# 362_MiniProj_FullBoard.net
KiCad netlist of a schematic drawn in EAGLE
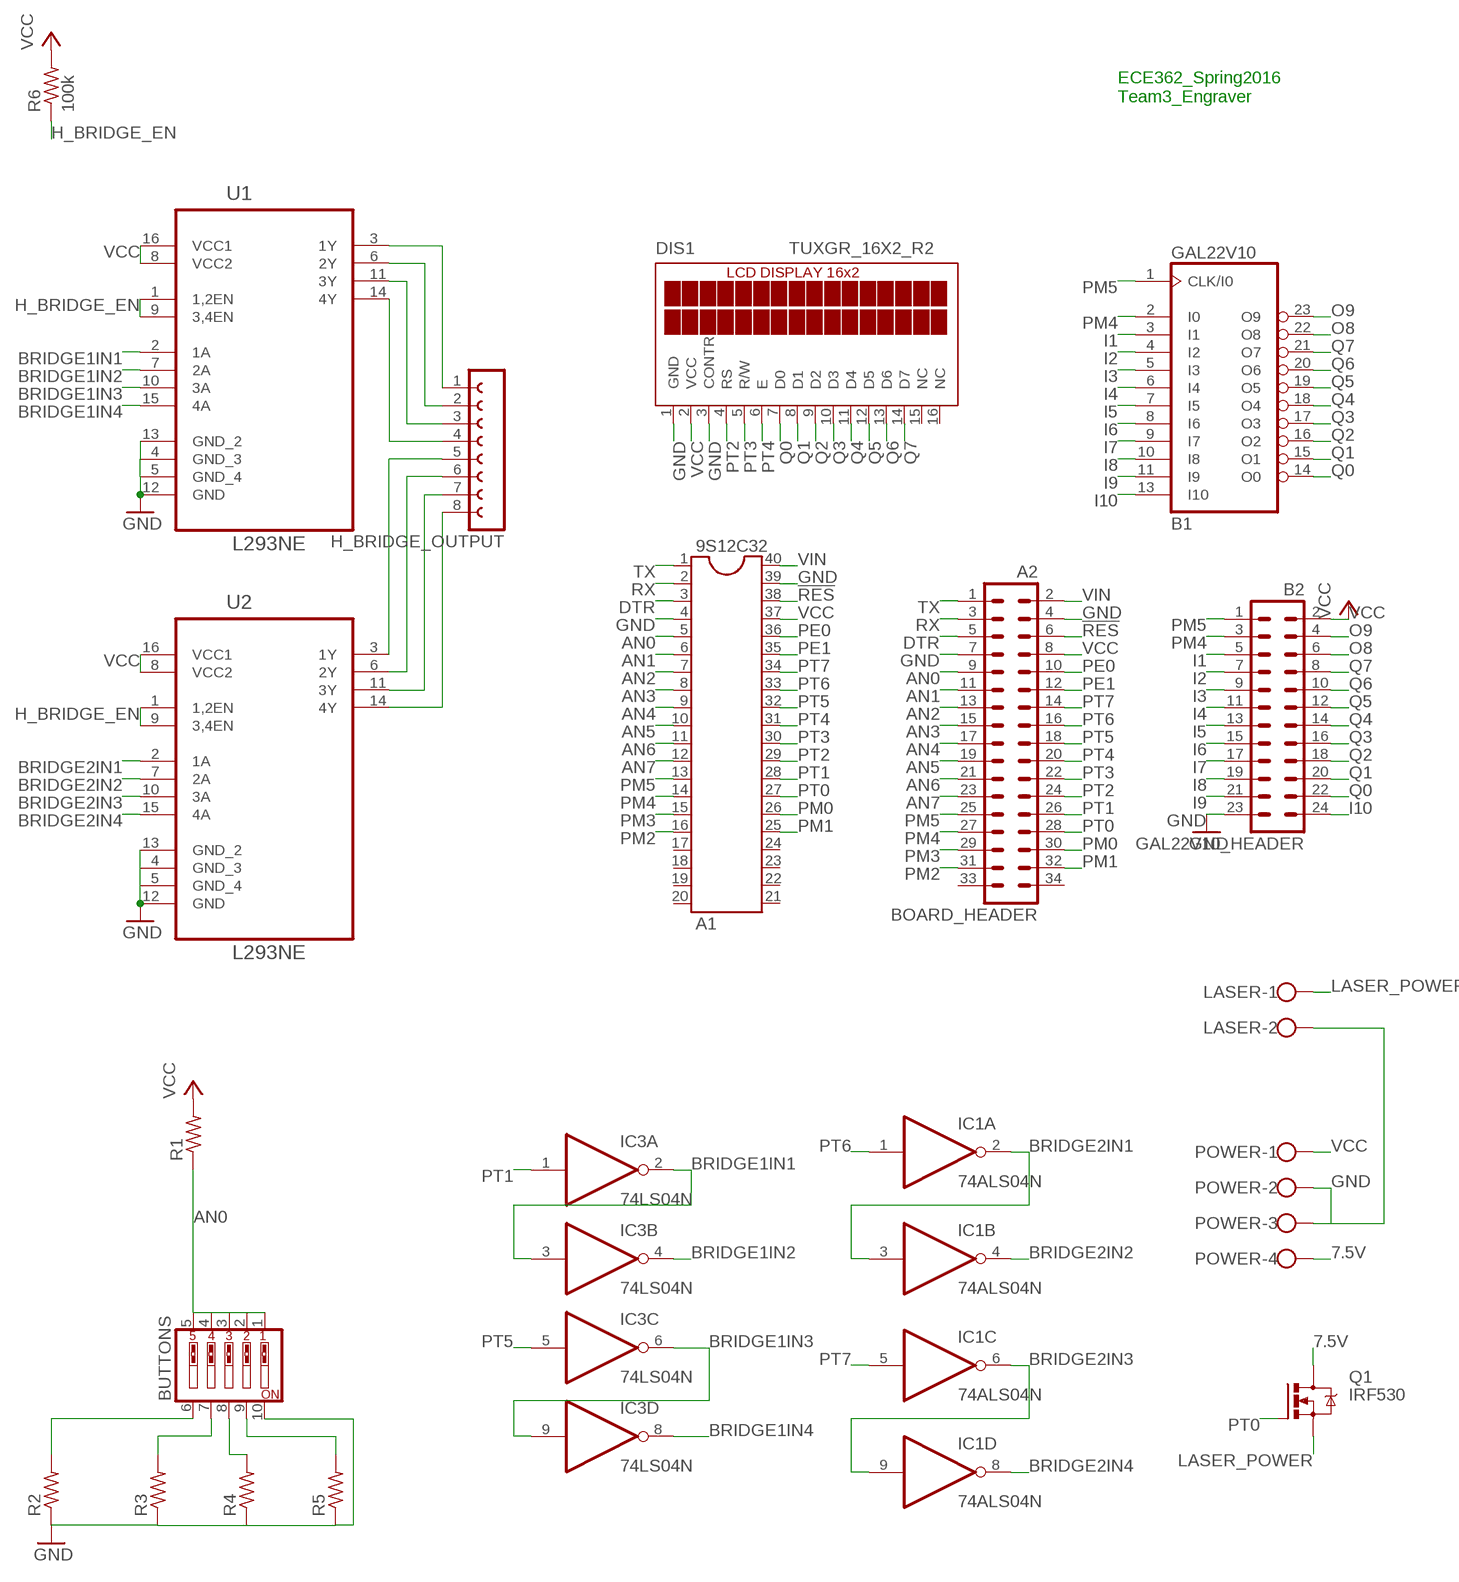
[diagram p0: schematic, sheet 1]

(export (version "E")
  (design (tool "Eeschema 10.0.6"))
  (components
    (comp (ref "9S12C32")
      (value "A1")
      (footprint "eagle-import:DIL40")
      (libsource (lib "eagle-import") (part "DIL40"))
    )
    (comp (ref "BOARD_HEADER")
      (value "A2")
      (footprint "eagle-import:MA17-2")
      (libsource (lib "eagle-import") (part "MA17-2"))
    )
    (comp (ref "BUTTONS")
      (value "SW_DIP-5")
      (footprint "eagle-import:EDG-05")
      (libsource (lib "eagle-import") (part "SW_DIP-5"))
    )
    (comp (ref "DIS1")
      (value "TUXGR_16X2_R2")
      (footprint "eagle-import:TUXGR_16X2_R2")
      (libsource (lib "eagle-import") (part "TUXGR_16X2_R2"))
    )
    (comp (ref "GAL22V10")
      (value "B1")
      (footprint "eagle-import:DIL24-3")
      (fields (field (name "MPN") "GAL22V10D-7LPN"))
      (libsource (lib "eagle-import") (part "22V10"))
    )
    (comp (ref "GAL22V10_HEADER")
      (value "B2")
      (footprint "eagle-import:MA12-2")
      (libsource (lib "eagle-import") (part "MA12-2"))
    )
    (comp (ref "H_BRIDGE_OUTPUT")
      (value "FE08-1")
      (footprint "eagle-import:FE08")
      (libsource (lib "eagle-import") (part "FE08-1"))
    )
    (comp (ref "IC1")
      (value "74ALS04N")
      (footprint "eagle-import:DIL14")
      (libsource (lib "eagle-import") (part "7404NALS"))
    )
    (comp (ref "IC3")
      (value "74LS04N")
      (footprint "eagle-import:DIL14")
      (libsource (lib "eagle-import") (part "74xx-us_7404NLS"))
    )
    (comp (ref "LASER")
      (value "W237-102")
      (footprint "eagle-import:W237-102")
      (fields (field (name "MPN") "237-102"))
      (libsource (lib "eagle-import") (part "W237-102"))
    )
    (comp (ref "POWER")
      (value "W239-104")
      (footprint "eagle-import:W239-104")
      (libsource (lib "eagle-import") (part "W239-104"))
    )
    (comp (ref "Q1")
      (value "IRF530")
      (footprint "eagle-import:TO220BV")
      (libsource (lib "eagle-import") (part "IRF530"))
    )
    (comp (ref "R1")
      (value "R-US_0207/10")
      (footprint "eagle-import:0207_10")
      (libsource (lib "eagle-import") (part "R-US_0207/10"))
    )
    (comp (ref "R2")
      (value "R-US_0207/10")
      (footprint "eagle-import:0207_10")
      (libsource (lib "eagle-import") (part "R-US_0207/10"))
    )
    (comp (ref "R3")
      (value "R-US_0207/10")
      (footprint "eagle-import:0207_10")
      (libsource (lib "eagle-import") (part "R-US_0207/10"))
    )
    (comp (ref "R4")
      (value "R-US_0207/10")
      (footprint "eagle-import:0207_10")
      (libsource (lib "eagle-import") (part "R-US_0207/10"))
    )
    (comp (ref "R5")
      (value "R-US_0207/10")
      (footprint "eagle-import:0207_10")
      (libsource (lib "eagle-import") (part "R-US_0207/10"))
    )
    (comp (ref "R6")
      (value "100k")
      (footprint "eagle-import:0207_10")
      (libsource (lib "eagle-import") (part "R-US_0207/10"))
    )
    (comp (ref "U1")
      (value "L293NE")
      (footprint "eagle-import:DIP254P762X508-16")
      (libsource (lib "eagle-import") (part "L293NE"))
    )
    (comp (ref "U2")
      (value "L293NE")
      (footprint "eagle-import:DIP254P762X508-16")
      (libsource (lib "eagle-import") (part "L293NE"))
    )
  )
  (nets
    (net (code "1") (name "/7.5V") (class "Default")
      (node (ref "POWER") (pin "4") (pinfunction "KL_4") (pintype "passive"))
      (node (ref "Q1") (pin "D") (pinfunction "D_D") (pintype "passive"))
    )
    (net (code "2") (name "/AN0") (class "Default")
      (node (ref "9S12C32") (pin "5") (pinfunction "5_5") (pintype "passive"))
      (node (ref "BOARD_HEADER") (pin "9") (pinfunction "9_9") (pintype "passive"))
      (node (ref "BUTTONS") (pin "1") (pinfunction "1_1") (pintype "passive"))
      (node (ref "BUTTONS") (pin "2") (pinfunction "2_2") (pintype "passive"))
      (node (ref "BUTTONS") (pin "3") (pinfunction "3_3") (pintype "passive"))
      (node (ref "BUTTONS") (pin "4") (pinfunction "4_4") (pintype "passive"))
      (node (ref "BUTTONS") (pin "5") (pinfunction "5_5") (pintype "passive"))
      (node (ref "R1") (pin "1") (pinfunction "1_1") (pintype "passive"))
    )
    (net (code "3") (name "/AN1") (class "Default")
      (node (ref "9S12C32") (pin "6") (pinfunction "6_6") (pintype "passive"))
      (node (ref "BOARD_HEADER") (pin "11") (pinfunction "11_11") (pintype "passive"))
    )
    (net (code "4") (name "/AN2") (class "Default")
      (node (ref "9S12C32") (pin "7") (pinfunction "7_7") (pintype "passive"))
      (node (ref "BOARD_HEADER") (pin "13") (pinfunction "13_13") (pintype "passive"))
    )
    (net (code "5") (name "/AN3") (class "Default")
      (node (ref "9S12C32") (pin "8") (pinfunction "8_8") (pintype "passive"))
      (node (ref "BOARD_HEADER") (pin "15") (pinfunction "15_15") (pintype "passive"))
    )
    (net (code "6") (name "/AN4") (class "Default")
      (node (ref "9S12C32") (pin "9") (pinfunction "9_9") (pintype "passive"))
      (node (ref "BOARD_HEADER") (pin "17") (pinfunction "17_17") (pintype "passive"))
    )
    (net (code "7") (name "/AN5") (class "Default")
      (node (ref "9S12C32") (pin "10") (pinfunction "10_10") (pintype "passive"))
      (node (ref "BOARD_HEADER") (pin "19") (pinfunction "19_19") (pintype "passive"))
    )
    (net (code "8") (name "/AN6") (class "Default")
      (node (ref "9S12C32") (pin "11") (pinfunction "11_11") (pintype "passive"))
      (node (ref "BOARD_HEADER") (pin "21") (pinfunction "21_21") (pintype "passive"))
    )
    (net (code "9") (name "/AN7") (class "Default")
      (node (ref "9S12C32") (pin "12") (pinfunction "12_12") (pintype "passive"))
      (node (ref "BOARD_HEADER") (pin "23") (pinfunction "23_23") (pintype "passive"))
    )
    (net (code "10") (name "/BRIDGE1IN1") (class "Default")
      (node (ref "IC3") (pin "2") (pinfunction "O_2") (pintype "output"))
      (node (ref "IC3") (pin "3") (pinfunction "I_3") (pintype "input"))
      (node (ref "U1") (pin "2") (pinfunction "1A_2") (pintype "input"))
    )
    (net (code "11") (name "/BRIDGE1IN2") (class "Default")
      (node (ref "IC3") (pin "4") (pinfunction "O_4") (pintype "output"))
      (node (ref "U1") (pin "7") (pinfunction "2A_7") (pintype "input"))
    )
    (net (code "12") (name "/BRIDGE1IN3") (class "Default")
      (node (ref "IC3") (pin "6") (pinfunction "O_6") (pintype "output"))
      (node (ref "IC3") (pin "9") (pinfunction "I_9") (pintype "input"))
      (node (ref "U1") (pin "10") (pinfunction "3A_10") (pintype "input"))
    )
    (net (code "13") (name "/BRIDGE1IN4") (class "Default")
      (node (ref "IC3") (pin "8") (pinfunction "O_8") (pintype "output"))
      (node (ref "U1") (pin "15") (pinfunction "4A_15") (pintype "input"))
    )
    (net (code "14") (name "/BRIDGE2IN1") (class "Default")
      (node (ref "IC1") (pin "2") (pinfunction "O_2") (pintype "output"))
      (node (ref "IC1") (pin "3") (pinfunction "I_3") (pintype "input"))
      (node (ref "U2") (pin "2") (pinfunction "1A_2") (pintype "input"))
    )
    (net (code "15") (name "/BRIDGE2IN2") (class "Default")
      (node (ref "IC1") (pin "4") (pinfunction "O_4") (pintype "output"))
      (node (ref "U2") (pin "7") (pinfunction "2A_7") (pintype "input"))
    )
    (net (code "16") (name "/BRIDGE2IN3") (class "Default")
      (node (ref "IC1") (pin "6") (pinfunction "O_6") (pintype "output"))
      (node (ref "IC1") (pin "9") (pinfunction "I_9") (pintype "input"))
      (node (ref "U2") (pin "10") (pinfunction "3A_10") (pintype "input"))
    )
    (net (code "17") (name "/BRIDGE2IN4") (class "Default")
      (node (ref "IC1") (pin "8") (pinfunction "O_8") (pintype "output"))
      (node (ref "U2") (pin "15") (pinfunction "4A_15") (pintype "input"))
    )
    (net (code "18") (name "/DTR") (class "Default")
      (node (ref "9S12C32") (pin "3") (pinfunction "3_3") (pintype "passive"))
      (node (ref "BOARD_HEADER") (pin "5") (pinfunction "5_5") (pintype "passive"))
    )
    (net (code "19") (name "/H_BRIDGE_EN") (class "Default")
      (node (ref "R6") (pin "1") (pinfunction "1_1") (pintype "passive"))
      (node (ref "U1") (pin "1") (pinfunction "1,2EN_1") (pintype "input"))
      (node (ref "U1") (pin "9") (pinfunction "3,4EN_9") (pintype "input"))
      (node (ref "U2") (pin "1") (pinfunction "1,2EN_1") (pintype "input"))
      (node (ref "U2") (pin "9") (pinfunction "3,4EN_9") (pintype "input"))
    )
    (net (code "20") (name "/I1") (class "Default")
      (node (ref "GAL22V10") (pin "3") (pinfunction "I1_3") (pintype "input"))
      (node (ref "GAL22V10_HEADER") (pin "5") (pinfunction "5_5") (pintype "passive"))
    )
    (net (code "21") (name "/I2") (class "Default")
      (node (ref "GAL22V10") (pin "4") (pinfunction "I2_4") (pintype "input"))
      (node (ref "GAL22V10_HEADER") (pin "7") (pinfunction "7_7") (pintype "passive"))
    )
    (net (code "22") (name "/I3") (class "Default")
      (node (ref "GAL22V10") (pin "5") (pinfunction "I3_5") (pintype "input"))
      (node (ref "GAL22V10_HEADER") (pin "9") (pinfunction "9_9") (pintype "passive"))
    )
    (net (code "23") (name "/I4") (class "Default")
      (node (ref "GAL22V10") (pin "6") (pinfunction "I4_6") (pintype "input"))
      (node (ref "GAL22V10_HEADER") (pin "11") (pinfunction "11_11") (pintype "passive"))
    )
    (net (code "24") (name "/I5") (class "Default")
      (node (ref "GAL22V10") (pin "7") (pinfunction "I5_7") (pintype "input"))
      (node (ref "GAL22V10_HEADER") (pin "13") (pinfunction "13_13") (pintype "passive"))
    )
    (net (code "25") (name "/I6") (class "Default")
      (node (ref "GAL22V10") (pin "8") (pinfunction "I6_8") (pintype "input"))
      (node (ref "GAL22V10_HEADER") (pin "15") (pinfunction "15_15") (pintype "passive"))
    )
    (net (code "26") (name "/I7") (class "Default")
      (node (ref "GAL22V10") (pin "9") (pinfunction "I7_9") (pintype "input"))
      (node (ref "GAL22V10_HEADER") (pin "17") (pinfunction "17_17") (pintype "passive"))
    )
    (net (code "27") (name "/I8") (class "Default")
      (node (ref "GAL22V10") (pin "10") (pinfunction "I8_10") (pintype "input"))
      (node (ref "GAL22V10_HEADER") (pin "19") (pinfunction "19_19") (pintype "passive"))
    )
    (net (code "28") (name "/I9") (class "Default")
      (node (ref "GAL22V10") (pin "11") (pinfunction "I9_11") (pintype "input"))
      (node (ref "GAL22V10_HEADER") (pin "21") (pinfunction "21_21") (pintype "passive"))
    )
    (net (code "29") (name "/I10") (class "Default")
      (node (ref "GAL22V10") (pin "13") (pinfunction "I10_13") (pintype "input"))
      (node (ref "GAL22V10_HEADER") (pin "24") (pinfunction "24_24") (pintype "passive"))
    )
    (net (code "30") (name "/LASER_POWER") (class "Default")
      (node (ref "LASER") (pin "1") (pinfunction "KL_1") (pintype "passive"))
      (node (ref "Q1") (pin "S") (pinfunction "S_S") (pintype "passive"))
    )
    (net (code "31") (name "/O8") (class "Default")
      (node (ref "GAL22V10") (pin "22") (pinfunction "O8_22") (pintype "bidirectional"))
      (node (ref "GAL22V10_HEADER") (pin "6") (pinfunction "6_6") (pintype "passive"))
    )
    (net (code "32") (name "/O9") (class "Default")
      (node (ref "GAL22V10") (pin "23") (pinfunction "O9_23") (pintype "bidirectional"))
      (node (ref "GAL22V10_HEADER") (pin "4") (pinfunction "4_4") (pintype "passive"))
    )
    (net (code "33") (name "/PE0") (class "Default")
      (node (ref "9S12C32") (pin "36") (pinfunction "36_36") (pintype "passive"))
      (node (ref "BOARD_HEADER") (pin "10") (pinfunction "10_10") (pintype "passive"))
    )
    (net (code "34") (name "/PE1") (class "Default")
      (node (ref "9S12C32") (pin "35") (pinfunction "35_35") (pintype "passive"))
      (node (ref "BOARD_HEADER") (pin "12") (pinfunction "12_12") (pintype "passive"))
    )
    (net (code "35") (name "/PM0") (class "Default")
      (node (ref "9S12C32") (pin "26") (pinfunction "26_26") (pintype "passive"))
      (node (ref "BOARD_HEADER") (pin "30") (pinfunction "30_30") (pintype "passive"))
    )
    (net (code "36") (name "/PM1") (class "Default")
      (node (ref "9S12C32") (pin "25") (pinfunction "25_25") (pintype "passive"))
      (node (ref "BOARD_HEADER") (pin "32") (pinfunction "32_32") (pintype "passive"))
    )
    (net (code "37") (name "/PM2") (class "Default")
      (node (ref "9S12C32") (pin "16") (pinfunction "16_16") (pintype "passive"))
      (node (ref "BOARD_HEADER") (pin "31") (pinfunction "31_31") (pintype "passive"))
    )
    (net (code "38") (name "/PM3") (class "Default")
      (node (ref "9S12C32") (pin "15") (pinfunction "15_15") (pintype "passive"))
      (node (ref "BOARD_HEADER") (pin "29") (pinfunction "29_29") (pintype "passive"))
    )
    (net (code "39") (name "/PM4") (class "Default")
      (node (ref "9S12C32") (pin "14") (pinfunction "14_14") (pintype "passive"))
      (node (ref "BOARD_HEADER") (pin "27") (pinfunction "27_27") (pintype "passive"))
      (node (ref "GAL22V10") (pin "2") (pinfunction "I0_2") (pintype "input"))
      (node (ref "GAL22V10_HEADER") (pin "3") (pinfunction "3_3") (pintype "passive"))
    )
    (net (code "40") (name "/PM5") (class "Default")
      (node (ref "9S12C32") (pin "13") (pinfunction "13_13") (pintype "passive"))
      (node (ref "BOARD_HEADER") (pin "25") (pinfunction "25_25") (pintype "passive"))
      (node (ref "GAL22V10") (pin "1") (pinfunction "CLK/I0_1") (pintype "input"))
      (node (ref "GAL22V10_HEADER") (pin "1") (pinfunction "1_1") (pintype "passive"))
    )
    (net (code "41") (name "/PT0") (class "Default")
      (node (ref "9S12C32") (pin "27") (pinfunction "27_27") (pintype "passive"))
      (node (ref "BOARD_HEADER") (pin "28") (pinfunction "28_28") (pintype "passive"))
      (node (ref "Q1") (pin "G") (pinfunction "G_G") (pintype "passive"))
    )
    (net (code "42") (name "/PT1") (class "Default")
      (node (ref "9S12C32") (pin "28") (pinfunction "28_28") (pintype "passive"))
      (node (ref "BOARD_HEADER") (pin "26") (pinfunction "26_26") (pintype "passive"))
      (node (ref "IC3") (pin "1") (pinfunction "I_1") (pintype "input"))
    )
    (net (code "43") (name "/PT2") (class "Default")
      (node (ref "9S12C32") (pin "29") (pinfunction "29_29") (pintype "passive"))
      (node (ref "BOARD_HEADER") (pin "24") (pinfunction "24_24") (pintype "passive"))
      (node (ref "DIS1") (pin "4") (pinfunction "RS_4") (pintype "input"))
    )
    (net (code "44") (name "/PT3") (class "Default")
      (node (ref "9S12C32") (pin "30") (pinfunction "30_30") (pintype "passive"))
      (node (ref "BOARD_HEADER") (pin "22") (pinfunction "22_22") (pintype "passive"))
      (node (ref "DIS1") (pin "5") (pinfunction "R/W_5") (pintype "input"))
    )
    (net (code "45") (name "/PT4") (class "Default")
      (node (ref "9S12C32") (pin "31") (pinfunction "31_31") (pintype "passive"))
      (node (ref "BOARD_HEADER") (pin "20") (pinfunction "20_20") (pintype "passive"))
      (node (ref "DIS1") (pin "6") (pinfunction "E_6") (pintype "input"))
    )
    (net (code "46") (name "/PT5") (class "Default")
      (node (ref "9S12C32") (pin "32") (pinfunction "32_32") (pintype "passive"))
      (node (ref "BOARD_HEADER") (pin "18") (pinfunction "18_18") (pintype "passive"))
      (node (ref "IC3") (pin "5") (pinfunction "I_5") (pintype "input"))
    )
    (net (code "47") (name "/PT6") (class "Default")
      (node (ref "9S12C32") (pin "33") (pinfunction "33_33") (pintype "passive"))
      (node (ref "BOARD_HEADER") (pin "16") (pinfunction "16_16") (pintype "passive"))
      (node (ref "IC1") (pin "1") (pinfunction "I_1") (pintype "input"))
    )
    (net (code "48") (name "/PT7") (class "Default")
      (node (ref "9S12C32") (pin "34") (pinfunction "34_34") (pintype "passive"))
      (node (ref "BOARD_HEADER") (pin "14") (pinfunction "14_14") (pintype "passive"))
      (node (ref "IC1") (pin "5") (pinfunction "I_5") (pintype "input"))
    )
    (net (code "49") (name "/Q0") (class "Default")
      (node (ref "DIS1") (pin "7") (pinfunction "D0_7") (pintype "input"))
      (node (ref "GAL22V10") (pin "14") (pinfunction "O0_14") (pintype "bidirectional"))
      (node (ref "GAL22V10_HEADER") (pin "22") (pinfunction "22_22") (pintype "passive"))
    )
    (net (code "50") (name "/Q1") (class "Default")
      (node (ref "DIS1") (pin "8") (pinfunction "D1_8") (pintype "input"))
      (node (ref "GAL22V10") (pin "15") (pinfunction "O1_15") (pintype "bidirectional"))
      (node (ref "GAL22V10_HEADER") (pin "20") (pinfunction "20_20") (pintype "passive"))
    )
    (net (code "51") (name "/Q2") (class "Default")
      (node (ref "DIS1") (pin "9") (pinfunction "D2_9") (pintype "input"))
      (node (ref "GAL22V10") (pin "16") (pinfunction "O2_16") (pintype "bidirectional"))
      (node (ref "GAL22V10_HEADER") (pin "18") (pinfunction "18_18") (pintype "passive"))
    )
    (net (code "52") (name "/Q3") (class "Default")
      (node (ref "DIS1") (pin "10") (pinfunction "D3_10") (pintype "input"))
      (node (ref "GAL22V10") (pin "17") (pinfunction "O3_17") (pintype "bidirectional"))
      (node (ref "GAL22V10_HEADER") (pin "16") (pinfunction "16_16") (pintype "passive"))
    )
    (net (code "53") (name "/Q4") (class "Default")
      (node (ref "DIS1") (pin "11") (pinfunction "D4_11") (pintype "input"))
      (node (ref "GAL22V10") (pin "18") (pinfunction "O4_18") (pintype "bidirectional"))
      (node (ref "GAL22V10_HEADER") (pin "14") (pinfunction "14_14") (pintype "passive"))
    )
    (net (code "54") (name "/Q5") (class "Default")
      (node (ref "DIS1") (pin "12") (pinfunction "D5_12") (pintype "input"))
      (node (ref "GAL22V10") (pin "19") (pinfunction "O5_19") (pintype "bidirectional"))
      (node (ref "GAL22V10_HEADER") (pin "12") (pinfunction "12_12") (pintype "passive"))
    )
    (net (code "55") (name "/Q6") (class "Default")
      (node (ref "DIS1") (pin "13") (pinfunction "D6_13") (pintype "input"))
      (node (ref "GAL22V10") (pin "20") (pinfunction "O6_20") (pintype "bidirectional"))
      (node (ref "GAL22V10_HEADER") (pin "10") (pinfunction "10_10") (pintype "passive"))
    )
    (net (code "56") (name "/Q7") (class "Default")
      (node (ref "DIS1") (pin "14") (pinfunction "D7_14") (pintype "input"))
      (node (ref "GAL22V10") (pin "21") (pinfunction "O7_21") (pintype "bidirectional"))
      (node (ref "GAL22V10_HEADER") (pin "8") (pinfunction "8_8") (pintype "passive"))
    )
    (net (code "57") (name "/RX") (class "Default")
      (node (ref "9S12C32") (pin "2") (pinfunction "2_2") (pintype "passive"))
      (node (ref "BOARD_HEADER") (pin "3") (pinfunction "3_3") (pintype "passive"))
    )
    (net (code "58") (name "/TX") (class "Default")
      (node (ref "9S12C32") (pin "1") (pinfunction "1_1") (pintype "passive"))
      (node (ref "BOARD_HEADER") (pin "1") (pinfunction "1_1") (pintype "passive"))
    )
    (net (code "59") (name "/VIN") (class "Default")
      (node (ref "9S12C32") (pin "40") (pinfunction "40_40") (pintype "passive"))
      (node (ref "BOARD_HEADER") (pin "2") (pinfunction "2_2") (pintype "passive"))
    )
    (net (code "60") (name "/~{RES}") (class "Default")
      (node (ref "9S12C32") (pin "38") (pinfunction "38_38") (pintype "passive"))
      (node (ref "BOARD_HEADER") (pin "6") (pinfunction "6_6") (pintype "passive"))
    )
    (net (code "61") (name "GND") (class "Default")
      (node (ref "9S12C32") (pin "39") (pinfunction "39_39") (pintype "passive"))
      (node (ref "9S12C32") (pin "4") (pinfunction "4_4") (pintype "passive"))
      (node (ref "BOARD_HEADER") (pin "4") (pinfunction "4_4") (pintype "passive"))
      (node (ref "BOARD_HEADER") (pin "7") (pinfunction "7_7") (pintype "passive"))
      (node (ref "BUTTONS") (pin "10") (pinfunction "10_10") (pintype "passive"))
      (node (ref "DIS1") (pin "1") (pinfunction "GND_1") (pintype "power_in"))
      (node (ref "DIS1") (pin "3") (pinfunction "CONTR_3") (pintype "input"))
      (node (ref "GAL22V10_HEADER") (pin "23") (pinfunction "23_23") (pintype "passive"))
      (node (ref "LASER") (pin "2") (pinfunction "KL_2") (pintype "passive"))
      (node (ref "POWER") (pin "2") (pinfunction "KL_2") (pintype "passive"))
      (node (ref "POWER") (pin "3") (pinfunction "KL_3") (pintype "passive"))
      (node (ref "R2") (pin "1") (pinfunction "1_1") (pintype "passive"))
      (node (ref "R3") (pin "1") (pinfunction "1_1") (pintype "passive"))
      (node (ref "R4") (pin "1") (pinfunction "1_1") (pintype "passive"))
      (node (ref "R5") (pin "1") (pinfunction "1_1") (pintype "passive"))
      (node (ref "U1") (pin "12") (pinfunction "GND_12") (pintype "passive"))
      (node (ref "U1") (pin "13") (pinfunction "GND_2_13") (pintype "passive"))
      (node (ref "U1") (pin "4") (pinfunction "GND_3_4") (pintype "passive"))
      (node (ref "U1") (pin "5") (pinfunction "GND_4_5") (pintype "passive"))
      (node (ref "U2") (pin "12") (pinfunction "GND_12") (pintype "passive"))
      (node (ref "U2") (pin "13") (pinfunction "GND_2_13") (pintype "passive"))
      (node (ref "U2") (pin "4") (pinfunction "GND_3_4") (pintype "passive"))
      (node (ref "U2") (pin "5") (pinfunction "GND_4_5") (pintype "passive"))
    )
    (net (code "62") (name "Net-(BUTTONS-Pad6)") (class "Default")
      (node (ref "BUTTONS") (pin "6") (pinfunction "6_6") (pintype "passive"))
      (node (ref "R2") (pin "2") (pinfunction "2_2") (pintype "passive"))
    )
    (net (code "63") (name "Net-(BUTTONS-Pad7)") (class "Default")
      (node (ref "BUTTONS") (pin "7") (pinfunction "7_7") (pintype "passive"))
      (node (ref "R3") (pin "2") (pinfunction "2_2") (pintype "passive"))
    )
    (net (code "64") (name "Net-(BUTTONS-Pad8)") (class "Default")
      (node (ref "BUTTONS") (pin "8") (pinfunction "8_8") (pintype "passive"))
      (node (ref "R4") (pin "2") (pinfunction "2_2") (pintype "passive"))
    )
    (net (code "65") (name "Net-(BUTTONS-Pad9)") (class "Default")
      (node (ref "BUTTONS") (pin "9") (pinfunction "9_9") (pintype "passive"))
      (node (ref "R5") (pin "2") (pinfunction "2_2") (pintype "passive"))
    )
    (net (code "66") (name "Net-(U1-1Y)") (class "Default")
      (node (ref "H_BRIDGE_OUTPUT") (pin "1") (pinfunction "1_1") (pintype "passive"))
      (node (ref "U1") (pin "3") (pinfunction "1Y_3") (pintype "output"))
    )
    (net (code "67") (name "Net-(U1-2Y)") (class "Default")
      (node (ref "H_BRIDGE_OUTPUT") (pin "2") (pinfunction "2_2") (pintype "passive"))
      (node (ref "U1") (pin "6") (pinfunction "2Y_6") (pintype "output"))
    )
    (net (code "68") (name "Net-(U1-3Y)") (class "Default")
      (node (ref "H_BRIDGE_OUTPUT") (pin "3") (pinfunction "3_3") (pintype "passive"))
      (node (ref "U1") (pin "11") (pinfunction "3Y_11") (pintype "output"))
    )
    (net (code "69") (name "Net-(U1-4Y)") (class "Default")
      (node (ref "H_BRIDGE_OUTPUT") (pin "4") (pinfunction "4_4") (pintype "passive"))
      (node (ref "U1") (pin "14") (pinfunction "4Y_14") (pintype "output"))
    )
    (net (code "70") (name "Net-(U2-1Y)") (class "Default")
      (node (ref "H_BRIDGE_OUTPUT") (pin "5") (pinfunction "5_5") (pintype "passive"))
      (node (ref "U2") (pin "3") (pinfunction "1Y_3") (pintype "output"))
    )
    (net (code "71") (name "Net-(U2-2Y)") (class "Default")
      (node (ref "H_BRIDGE_OUTPUT") (pin "6") (pinfunction "6_6") (pintype "passive"))
      (node (ref "U2") (pin "6") (pinfunction "2Y_6") (pintype "output"))
    )
    (net (code "72") (name "Net-(U2-3Y)") (class "Default")
      (node (ref "H_BRIDGE_OUTPUT") (pin "7") (pinfunction "7_7") (pintype "passive"))
      (node (ref "U2") (pin "11") (pinfunction "3Y_11") (pintype "output"))
    )
    (net (code "73") (name "Net-(U2-4Y)") (class "Default")
      (node (ref "H_BRIDGE_OUTPUT") (pin "8") (pinfunction "8_8") (pintype "passive"))
      (node (ref "U2") (pin "14") (pinfunction "4Y_14") (pintype "output"))
    )
    (net (code "74") (name "VCC") (class "Default")
      (node (ref "9S12C32") (pin "37") (pinfunction "37_37") (pintype "passive"))
      (node (ref "BOARD_HEADER") (pin "8") (pinfunction "8_8") (pintype "passive"))
      (node (ref "DIS1") (pin "2") (pinfunction "VCC_2") (pintype "power_in"))
      (node (ref "GAL22V10_HEADER") (pin "2") (pinfunction "2_2") (pintype "passive"))
      (node (ref "POWER") (pin "1") (pinfunction "KL_1") (pintype "passive"))
      (node (ref "R1") (pin "2") (pinfunction "2_2") (pintype "passive"))
      (node (ref "R6") (pin "2") (pinfunction "2_2") (pintype "passive"))
      (node (ref "U1") (pin "16") (pinfunction "VCC1_16") (pintype "power_in"))
      (node (ref "U1") (pin "8") (pinfunction "VCC2_8") (pintype "power_in"))
      (node (ref "U2") (pin "16") (pinfunction "VCC1_16") (pintype "power_in"))
      (node (ref "U2") (pin "8") (pinfunction "VCC2_8") (pintype "power_in"))
    )
    (net (code "75") (name "unconnected-(9S12C32-Pad17)") (class "Default")
      (node (ref "9S12C32") (pin "17") (pinfunction "17_17") (pintype "passive"))
    )
    (net (code "76") (name "unconnected-(9S12C32-Pad18)") (class "Default")
      (node (ref "9S12C32") (pin "18") (pinfunction "18_18") (pintype "passive"))
    )
    (net (code "77") (name "unconnected-(9S12C32-Pad19)") (class "Default")
      (node (ref "9S12C32") (pin "19") (pinfunction "19_19") (pintype "passive"))
    )
    (net (code "78") (name "unconnected-(9S12C32-Pad20)") (class "Default")
      (node (ref "9S12C32") (pin "20") (pinfunction "20_20") (pintype "passive"))
    )
    (net (code "79") (name "unconnected-(9S12C32-Pad21)") (class "Default")
      (node (ref "9S12C32") (pin "21") (pinfunction "21_21") (pintype "passive"))
    )
    (net (code "80") (name "unconnected-(9S12C32-Pad22)") (class "Default")
      (node (ref "9S12C32") (pin "22") (pinfunction "22_22") (pintype "passive"))
    )
    (net (code "81") (name "unconnected-(9S12C32-Pad23)") (class "Default")
      (node (ref "9S12C32") (pin "23") (pinfunction "23_23") (pintype "passive"))
    )
    (net (code "82") (name "unconnected-(9S12C32-Pad24)") (class "Default")
      (node (ref "9S12C32") (pin "24") (pinfunction "24_24") (pintype "passive"))
    )
    (net (code "83") (name "unconnected-(BOARD_HEADER-Pad33)") (class "Default")
      (node (ref "BOARD_HEADER") (pin "33") (pinfunction "33_33") (pintype "passive"))
    )
    (net (code "84") (name "unconnected-(BOARD_HEADER-Pad34)") (class "Default")
      (node (ref "BOARD_HEADER") (pin "34") (pinfunction "34_34") (pintype "passive"))
    )
    (net (code "85") (name "unconnected-(DIS1-NC-Pad15)") (class "Default")
      (node (ref "DIS1") (pin "15") (pinfunction "NC_15") (pintype "no_connect"))
    )
    (net (code "86") (name "unconnected-(DIS1-NC-Pad16)") (class "Default")
      (node (ref "DIS1") (pin "16") (pinfunction "NC_16") (pintype "no_connect"))
    )
  )
)
